# Protoboard.net
KiCad netlist of a schematic drawn in EAGLE
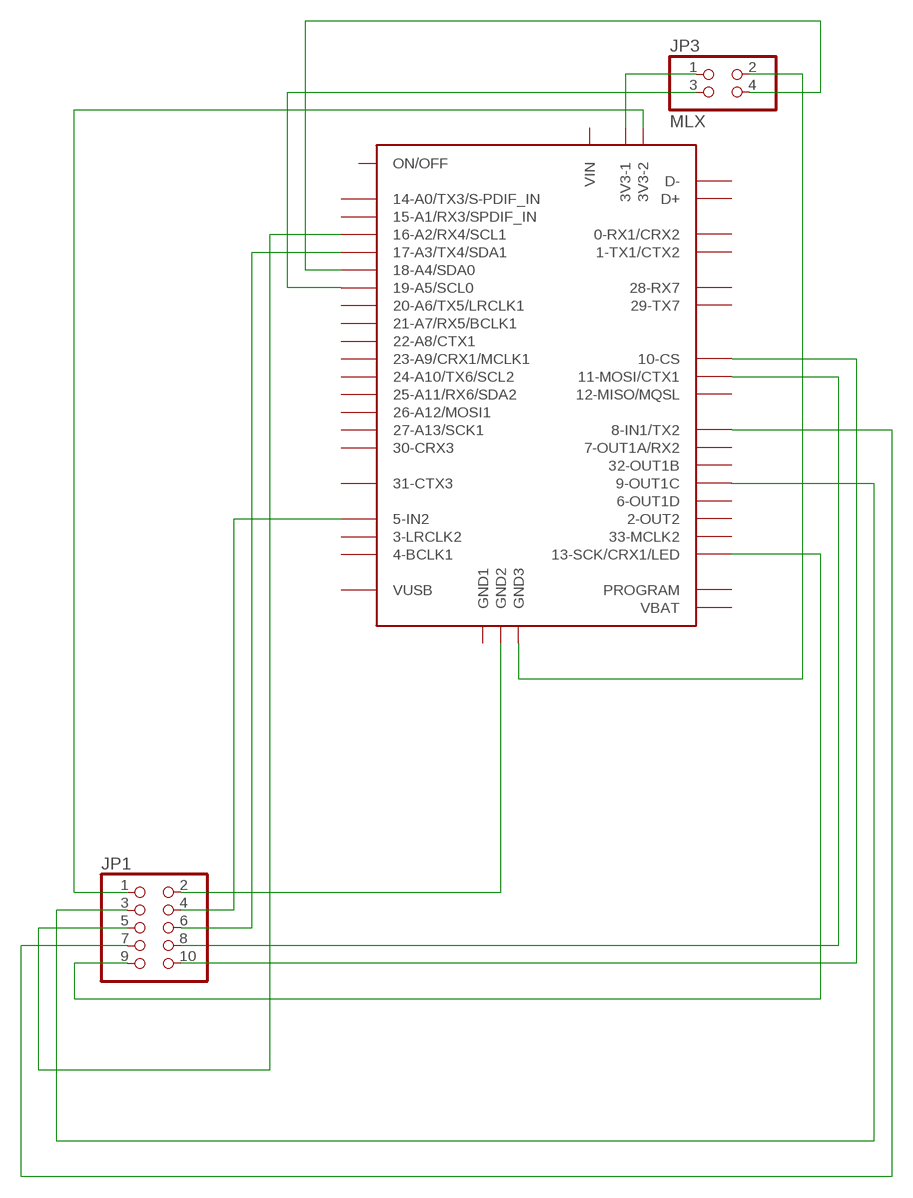
[diagram p0: schematic, sheet 1]

(export (version "E")
  (design (tool "Eeschema 10.0.6"))
  (components
    (comp (ref "JP1")
      (value "PINHD-2X5")
      (footprint "eagle-import:2X05")
      (libsource (lib "eagle-import") (part "PINHD-2X5"))
    )
    (comp (ref "JP3")
      (value "MLX")
      (footprint "eagle-import:2X02")
      (libsource (lib "eagle-import") (part "PINHD-2X2"))
    )
    (comp (ref "U$1")
      (value "TEENSY40")
      (footprint "eagle-import:TEENSY40")
      (libsource (lib "eagle-import") (part "TEENSY40"))
    )
  )
  (nets
    (net (code "1") (name "Net-(JP1-Pad1)") (class "Default")
      (node (ref "JP1") (pin "1") (pinfunction "1_1") (pintype "passive"))
      (node (ref "U$1") (pin "3V3-2") (pinfunction "3V3-2_3V3-2") (pintype "bidirectional"))
    )
    (net (code "2") (name "Net-(JP1-Pad2)") (class "Default")
      (node (ref "JP1") (pin "2") (pinfunction "2_2") (pintype "passive"))
      (node (ref "U$1") (pin "GND2") (pinfunction "GND2_GND2") (pintype "bidirectional"))
    )
    (net (code "3") (name "Net-(JP1-Pad3)") (class "Default")
      (node (ref "JP1") (pin "3") (pinfunction "3_3") (pintype "passive"))
      (node (ref "U$1") (pin "9-OUT1C") (pinfunction "9-OUT1C_9-OUT1C") (pintype "bidirectional"))
    )
    (net (code "4") (name "Net-(JP1-Pad4)") (class "Default")
      (node (ref "JP1") (pin "4") (pinfunction "4_4") (pintype "passive"))
      (node (ref "U$1") (pin "5-IN2") (pinfunction "5-IN2_5-IN2") (pintype "bidirectional"))
    )
    (net (code "5") (name "Net-(JP1-Pad5)") (class "Default")
      (node (ref "JP1") (pin "5") (pinfunction "5_5") (pintype "passive"))
      (node (ref "U$1") (pin "16-A2/RX4/SCL1") (pinfunction "16-A2/RX4/SCL1_16-A2/RX4/SCL1") (pintype "bidirectional"))
    )
    (net (code "6") (name "Net-(JP1-Pad6)") (class "Default")
      (node (ref "JP1") (pin "6") (pinfunction "6_6") (pintype "passive"))
      (node (ref "U$1") (pin "17-A3/TX4/SDA1") (pinfunction "17-A3/TX4/SDA1_17-A3/TX4/SDA1") (pintype "bidirectional"))
    )
    (net (code "7") (name "Net-(JP1-Pad8)") (class "Default")
      (node (ref "JP1") (pin "8") (pinfunction "8_8") (pintype "passive"))
      (node (ref "U$1") (pin "11-MOSI/CTX1") (pinfunction "11-MOSI/CTX1_11-MOSI/CTX1") (pintype "bidirectional"))
    )
    (net (code "8") (name "Net-(JP1-Pad9)") (class "Default")
      (node (ref "JP1") (pin "9") (pinfunction "9_9") (pintype "passive"))
      (node (ref "U$1") (pin "13-SCK/CRX1/LED") (pinfunction "13-SCK/CRX1/LED_13-SCK/CRX1/LED") (pintype "bidirectional"))
    )
    (net (code "9") (name "Net-(JP3-Pad1)") (class "Default")
      (node (ref "JP3") (pin "1") (pinfunction "1_1") (pintype "passive"))
      (node (ref "U$1") (pin "3V3-1") (pinfunction "3V3-1_3V3-1") (pintype "bidirectional"))
    )
    (net (code "10") (name "Net-(JP3-Pad2)") (class "Default")
      (node (ref "JP3") (pin "2") (pinfunction "2_2") (pintype "passive"))
      (node (ref "U$1") (pin "GND3") (pinfunction "GND3_GND3") (pintype "bidirectional"))
    )
    (net (code "11") (name "Net-(JP3-Pad3)") (class "Default")
      (node (ref "JP3") (pin "3") (pinfunction "3_3") (pintype "passive"))
      (node (ref "U$1") (pin "19-A5/SCL0") (pinfunction "19-A5/SCL0_19-A5/SCL0") (pintype "bidirectional"))
    )
    (net (code "12") (name "Net-(JP3-Pad4)") (class "Default")
      (node (ref "JP3") (pin "4") (pinfunction "4_4") (pintype "passive"))
      (node (ref "U$1") (pin "18-A4/SDA0") (pinfunction "18-A4/SDA0_18-A4/SDA0") (pintype "bidirectional"))
    )
    (net (code "13") (name "Net-(U$1-8-IN1{slash}TX2)") (class "Default")
      (node (ref "JP1") (pin "7") (pinfunction "7_7") (pintype "passive"))
      (node (ref "U$1") (pin "8-TX2/IN1") (pinfunction "8-IN1/TX2_8-TX2/IN1") (pintype "bidirectional"))
    )
    (net (code "14") (name "Net-(U$1-10-CS)") (class "Default")
      (node (ref "JP1") (pin "10") (pinfunction "10_10") (pintype "passive"))
      (node (ref "U$1") (pin "10-CS/MQSR") (pinfunction "10-CS_10-CS/MQSR") (pintype "bidirectional"))
    )
    (net (code "15") (name "unconnected-(U$1-0-RX1{slash}CRX2-Pad0-RX1)") (class "Default")
      (node (ref "U$1") (pin "0-RX1") (pinfunction "0-RX1/CRX2_0-RX1") (pintype "bidirectional"))
    )
    (net (code "16") (name "unconnected-(U$1-1-TX1{slash}CTX2-Pad1-TX1)") (class "Default")
      (node (ref "U$1") (pin "1-TX1") (pinfunction "1-TX1/CTX2_1-TX1") (pintype "bidirectional"))
    )
    (net (code "17") (name "unconnected-(U$1-4-BCLK1-Pad4-BCLK2)") (class "Default")
      (node (ref "U$1") (pin "4-BCLK2") (pinfunction "4-BCLK1_4-BCLK2") (pintype "bidirectional"))
    )
    (net (code "18") (name "unconnected-(U$1-7-OUT1A{slash}RX2-Pad7-RX2{slash}OUT1A)") (class "Default")
      (node (ref "U$1") (pin "7-RX2/OUT1A") (pinfunction "7-OUT1A/RX2_7-RX2/OUT1A") (pintype "bidirectional"))
    )
    (net (code "19") (name "unconnected-(U$1-12-MISO{slash}MQSL-Pad12-MIO{slash}MQSL)") (class "Default")
      (node (ref "U$1") (pin "12-MIO/MQSL") (pinfunction "12-MISO/MQSL_12-MIO/MQSL") (pintype "bidirectional"))
    )
    (net (code "20") (name "unconnected-(U$1-14-A0{slash}TX3{slash}S-PDIF_IN-Pad14-A0{slash}TX3{slash}S-PFI_OUT)") (class "Default")
      (node (ref "U$1") (pin "14-A0/TX3/S-PFI_OUT") (pinfunction "14-A0/TX3/S-PDIF_IN_14-A0/TX3/S-PFI_OUT") (pintype "bidirectional"))
    )
    (net (code "21") (name "unconnected-(U$1-15-A1{slash}RX3{slash}SPDIF_IN-Pad15-A1{slash}RX3{slash}S-PDIF_IN)") (class "Default")
      (node (ref "U$1") (pin "15-A1/RX3/S-PDIF_IN") (pinfunction "15-A1/RX3/SPDIF_IN_15-A1/RX3/S-PDIF_IN") (pintype "bidirectional"))
    )
    (net (code "22") (name "unconnected-(U$1-23-A9{slash}CRX1{slash}MCLK1-Pad23-A9{slash}CRX1{slash}CCLK1)") (class "Default")
      (node (ref "U$1") (pin "23-A9/CRX1/CCLK1") (pinfunction "23-A9/CRX1/MCLK1_23-A9/CRX1/CCLK1") (pintype "bidirectional"))
    )
    (net (code "23") (name "unconnected-(U$1-25-A11{slash}RX6{slash}SDA2-Pad25-A11{slash}SDA2)") (class "Default")
      (node (ref "U$1") (pin "25-A11/SDA2") (pinfunction "25-A11/RX6/SDA2_25-A11/SDA2") (pintype "bidirectional"))
    )
    (net (code "24") (name "unconnected-(U$1-32-OUT1B-Pad32-OUTB1)") (class "Default")
      (node (ref "U$1") (pin "32-OUTB1") (pinfunction "32-OUT1B_32-OUTB1") (pintype "bidirectional"))
    )
    (net (code "25") (name "unconnected-(U$1-Pad2-OUT2)") (class "Default")
      (node (ref "U$1") (pin "2-OUT2") (pinfunction "2-OUT2_2-OUT2") (pintype "bidirectional"))
    )
    (net (code "26") (name "unconnected-(U$1-Pad3-LRCLK2)") (class "Default")
      (node (ref "U$1") (pin "3-LRCLK2") (pinfunction "3-LRCLK2_3-LRCLK2") (pintype "bidirectional"))
    )
    (net (code "27") (name "unconnected-(U$1-Pad6-OUT1D)") (class "Default")
      (node (ref "U$1") (pin "6-OUT1D") (pinfunction "6-OUT1D_6-OUT1D") (pintype "bidirectional"))
    )
    (net (code "28") (name "unconnected-(U$1-Pad20-A6{slash}TX5{slash}LRCLK1)") (class "Default")
      (node (ref "U$1") (pin "20-A6/TX5/LRCLK1") (pinfunction "20-A6/TX5/LRCLK1_20-A6/TX5/LRCLK1") (pintype "bidirectional"))
    )
    (net (code "29") (name "unconnected-(U$1-Pad21-A7{slash}RX5{slash}BCLK1)") (class "Default")
      (node (ref "U$1") (pin "21-A7/RX5/BCLK1") (pinfunction "21-A7/RX5/BCLK1_21-A7/RX5/BCLK1") (pintype "bidirectional"))
    )
    (net (code "30") (name "unconnected-(U$1-Pad22-A8{slash}CTX1)") (class "Default")
      (node (ref "U$1") (pin "22-A8/CTX1") (pinfunction "22-A8/CTX1_22-A8/CTX1") (pintype "bidirectional"))
    )
    (net (code "31") (name "unconnected-(U$1-Pad24-A10{slash}TX6{slash}SCL2)") (class "Default")
      (node (ref "U$1") (pin "24-A10/TX6/SCL2") (pinfunction "24-A10/TX6/SCL2_24-A10/TX6/SCL2") (pintype "bidirectional"))
    )
    (net (code "32") (name "unconnected-(U$1-Pad26-A12{slash}MOSI1)") (class "Default")
      (node (ref "U$1") (pin "26-A12/MOSI1") (pinfunction "26-A12/MOSI1_26-A12/MOSI1") (pintype "bidirectional"))
    )
    (net (code "33") (name "unconnected-(U$1-Pad27-A13{slash}SCK1)") (class "Default")
      (node (ref "U$1") (pin "27-A13/SCK1") (pinfunction "27-A13/SCK1_27-A13/SCK1") (pintype "bidirectional"))
    )
    (net (code "34") (name "unconnected-(U$1-Pad28-RX7)") (class "Default")
      (node (ref "U$1") (pin "28-RX7") (pinfunction "28-RX7_28-RX7") (pintype "bidirectional"))
    )
    (net (code "35") (name "unconnected-(U$1-Pad29-TX7)") (class "Default")
      (node (ref "U$1") (pin "29-TX7") (pinfunction "29-TX7_29-TX7") (pintype "bidirectional"))
    )
    (net (code "36") (name "unconnected-(U$1-Pad30-CRX3)") (class "Default")
      (node (ref "U$1") (pin "30-CRX3") (pinfunction "30-CRX3_30-CRX3") (pintype "bidirectional"))
    )
    (net (code "37") (name "unconnected-(U$1-Pad31-CTX3)") (class "Default")
      (node (ref "U$1") (pin "31-CTX3") (pinfunction "31-CTX3_31-CTX3") (pintype "bidirectional"))
    )
    (net (code "38") (name "unconnected-(U$1-Pad33-MCLK2)") (class "Default")
      (node (ref "U$1") (pin "33-MCLK2") (pinfunction "33-MCLK2_33-MCLK2") (pintype "bidirectional"))
    )
    (net (code "39") (name "unconnected-(U$1-PadD+)") (class "Default")
      (node (ref "U$1") (pin "D+") (pinfunction "D+_D+") (pintype "bidirectional"))
    )
    (net (code "40") (name "unconnected-(U$1-PadD-)") (class "Default")
      (node (ref "U$1") (pin "D-") (pinfunction "D-_D-") (pintype "bidirectional"))
    )
    (net (code "41") (name "unconnected-(U$1-PadGND1)") (class "Default")
      (node (ref "U$1") (pin "GND1") (pinfunction "GND1_GND1") (pintype "bidirectional"))
    )
    (net (code "42") (name "unconnected-(U$1-PadON{slash}OFF)") (class "Default")
      (node (ref "U$1") (pin "ON/OFF") (pinfunction "ON/OFF_ON/OFF") (pintype "bidirectional"))
    )
    (net (code "43") (name "unconnected-(U$1-PadPROGRAM)") (class "Default")
      (node (ref "U$1") (pin "PROGRAM") (pinfunction "PROGRAM_PROGRAM") (pintype "bidirectional"))
    )
    (net (code "44") (name "unconnected-(U$1-PadVBAT)") (class "Default")
      (node (ref "U$1") (pin "VBAT") (pinfunction "VBAT_VBAT") (pintype "bidirectional"))
    )
    (net (code "45") (name "unconnected-(U$1-PadVIN)") (class "Default")
      (node (ref "U$1") (pin "VIN") (pinfunction "VIN_VIN") (pintype "bidirectional"))
    )
    (net (code "46") (name "unconnected-(U$1-PadVUSB)") (class "Default")
      (node (ref "U$1") (pin "VUSB") (pinfunction "VUSB_VUSB") (pintype "bidirectional"))
    )
  )
)
